# AVRI2CIO.net
KiCad netlist of a schematic drawn in EAGLE
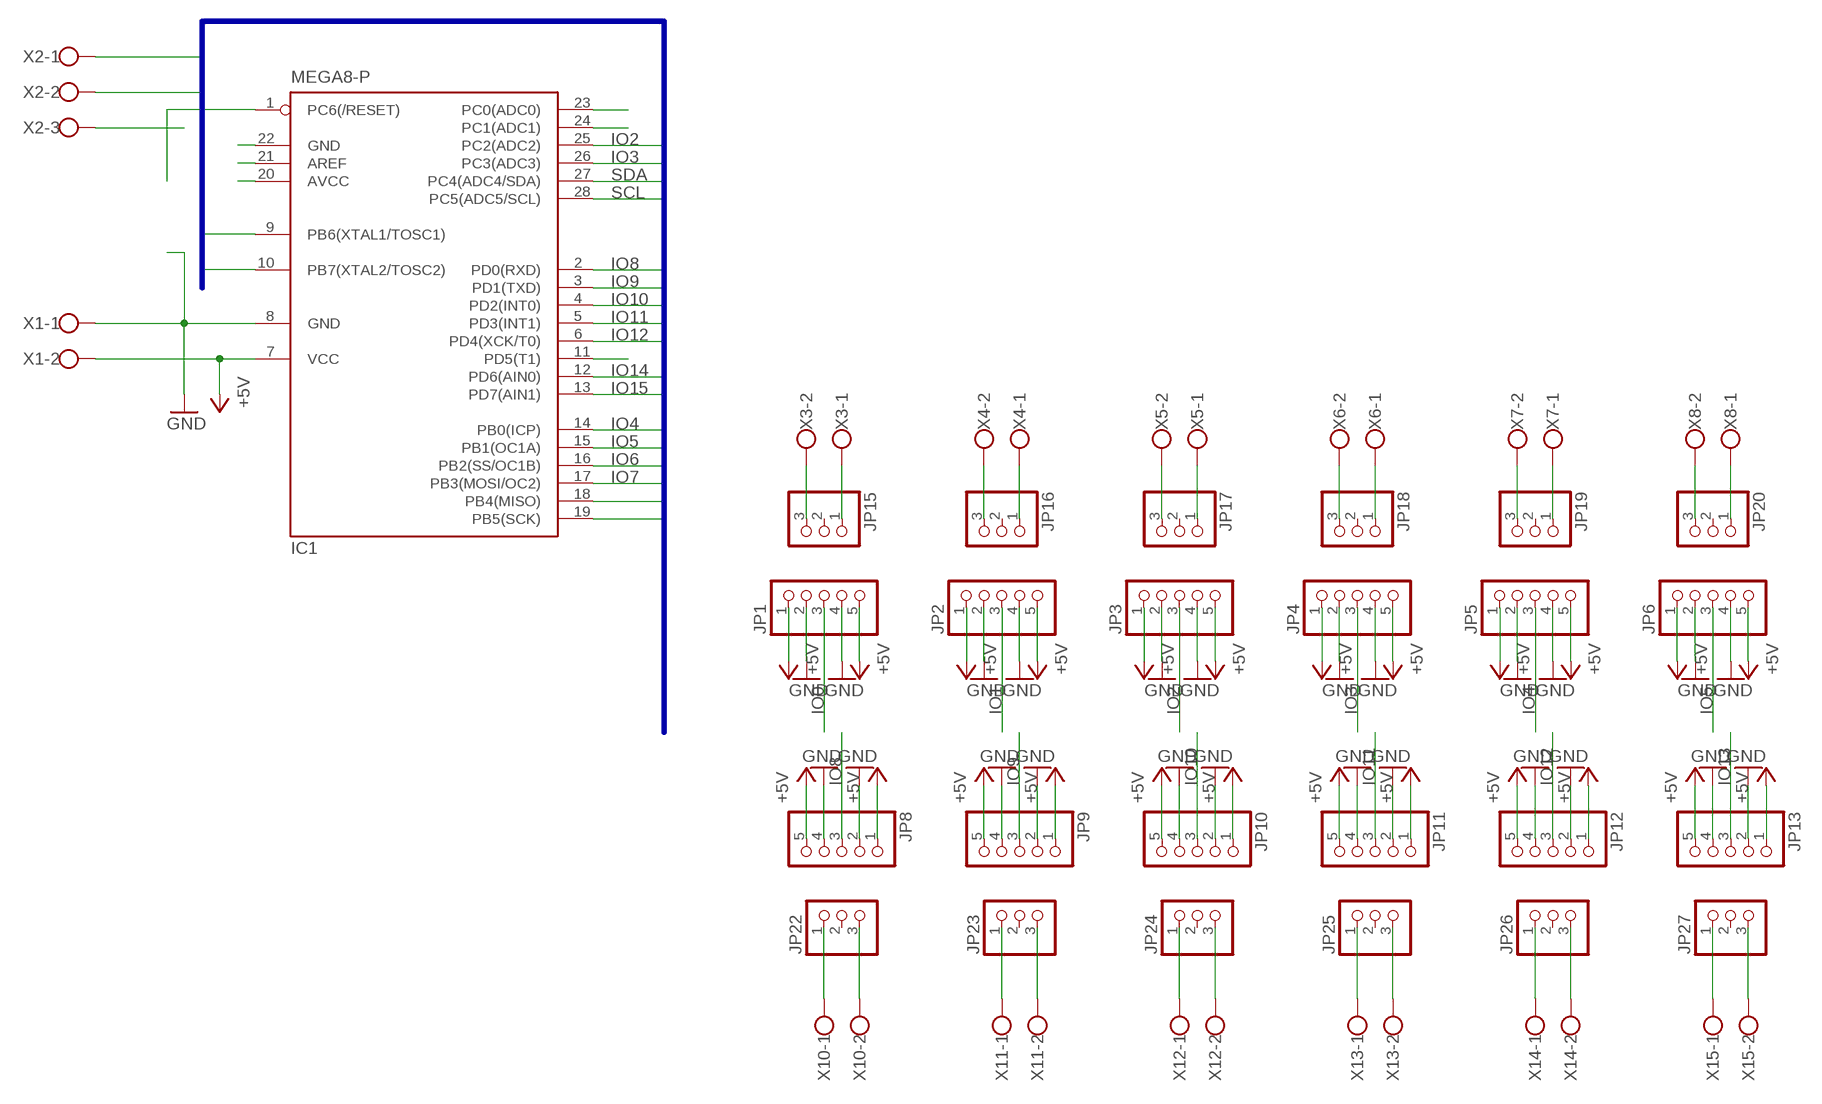
[diagram p0: schematic, sheet 1]

(export (version "E")
  (design (tool "Eeschema 10.0.6"))
  (components
    (comp (ref "IC1")
      (value "MEGA8-P")
      (footprint "eagle-import:DIL28-3")
      (libsource (lib "eagle-import") (part "MEGA8-P"))
    )
    (comp (ref "JP1")
      (value "PINHD-1X5")
      (footprint "eagle-import:1X05")
      (libsource (lib "eagle-import") (part "PINHD-1X5"))
    )
    (comp (ref "JP2")
      (value "PINHD-1X5")
      (footprint "eagle-import:1X05")
      (libsource (lib "eagle-import") (part "PINHD-1X5"))
    )
    (comp (ref "JP3")
      (value "PINHD-1X5")
      (footprint "eagle-import:1X05")
      (libsource (lib "eagle-import") (part "PINHD-1X5"))
    )
    (comp (ref "JP4")
      (value "PINHD-1X5")
      (footprint "eagle-import:1X05")
      (libsource (lib "eagle-import") (part "PINHD-1X5"))
    )
    (comp (ref "JP5")
      (value "PINHD-1X5")
      (footprint "eagle-import:1X05")
      (libsource (lib "eagle-import") (part "PINHD-1X5"))
    )
    (comp (ref "JP6")
      (value "PINHD-1X5")
      (footprint "eagle-import:1X05")
      (libsource (lib "eagle-import") (part "PINHD-1X5"))
    )
    (comp (ref "JP8")
      (value "PINHD-1X5")
      (footprint "eagle-import:1X05")
      (libsource (lib "eagle-import") (part "PINHD-1X5"))
    )
    (comp (ref "JP9")
      (value "PINHD-1X5")
      (footprint "eagle-import:1X05")
      (libsource (lib "eagle-import") (part "PINHD-1X5"))
    )
    (comp (ref "JP10")
      (value "PINHD-1X5")
      (footprint "eagle-import:1X05")
      (libsource (lib "eagle-import") (part "PINHD-1X5"))
    )
    (comp (ref "JP11")
      (value "PINHD-1X5")
      (footprint "eagle-import:1X05")
      (libsource (lib "eagle-import") (part "PINHD-1X5"))
    )
    (comp (ref "JP12")
      (value "PINHD-1X5")
      (footprint "eagle-import:1X05")
      (libsource (lib "eagle-import") (part "PINHD-1X5"))
    )
    (comp (ref "JP13")
      (value "PINHD-1X5")
      (footprint "eagle-import:1X05")
      (libsource (lib "eagle-import") (part "PINHD-1X5"))
    )
    (comp (ref "JP15")
      (value "PINHD-1X3")
      (footprint "eagle-import:1X03")
      (libsource (lib "eagle-import") (part "PINHD-1X3"))
    )
    (comp (ref "JP16")
      (value "PINHD-1X3")
      (footprint "eagle-import:1X03")
      (libsource (lib "eagle-import") (part "PINHD-1X3"))
    )
    (comp (ref "JP17")
      (value "PINHD-1X3")
      (footprint "eagle-import:1X03")
      (libsource (lib "eagle-import") (part "PINHD-1X3"))
    )
    (comp (ref "JP18")
      (value "PINHD-1X3")
      (footprint "eagle-import:1X03")
      (libsource (lib "eagle-import") (part "PINHD-1X3"))
    )
    (comp (ref "JP19")
      (value "PINHD-1X3")
      (footprint "eagle-import:1X03")
      (libsource (lib "eagle-import") (part "PINHD-1X3"))
    )
    (comp (ref "JP20")
      (value "PINHD-1X3")
      (footprint "eagle-import:1X03")
      (libsource (lib "eagle-import") (part "PINHD-1X3"))
    )
    (comp (ref "JP22")
      (value "PINHD-1X3")
      (footprint "eagle-import:1X03")
      (libsource (lib "eagle-import") (part "PINHD-1X3"))
    )
    (comp (ref "JP23")
      (value "PINHD-1X3")
      (footprint "eagle-import:1X03")
      (libsource (lib "eagle-import") (part "PINHD-1X3"))
    )
    (comp (ref "JP24")
      (value "PINHD-1X3")
      (footprint "eagle-import:1X03")
      (libsource (lib "eagle-import") (part "PINHD-1X3"))
    )
    (comp (ref "JP25")
      (value "PINHD-1X3")
      (footprint "eagle-import:1X03")
      (libsource (lib "eagle-import") (part "PINHD-1X3"))
    )
    (comp (ref "JP26")
      (value "PINHD-1X3")
      (footprint "eagle-import:1X03")
      (libsource (lib "eagle-import") (part "PINHD-1X3"))
    )
    (comp (ref "JP27")
      (value "PINHD-1X3")
      (footprint "eagle-import:1X03")
      (libsource (lib "eagle-import") (part "PINHD-1X3"))
    )
    (comp (ref "X1")
      (value "W237-102")
      (footprint "eagle-import:W237-102")
      (fields (field (name "MPN") "237-102"))
      (libsource (lib "eagle-import") (part "W237-102"))
    )
    (comp (ref "X2")
      (value "W237-103")
      (footprint "eagle-import:W237-103")
      (fields (field (name "MPN") "237-103"))
      (libsource (lib "eagle-import") (part "W237-103"))
    )
    (comp (ref "X3")
      (value "W237-102")
      (footprint "eagle-import:W237-102")
      (fields (field (name "MPN") "237-102"))
      (libsource (lib "eagle-import") (part "W237-102"))
    )
    (comp (ref "X4")
      (value "W237-102")
      (footprint "eagle-import:W237-102")
      (fields (field (name "MPN") "237-102"))
      (libsource (lib "eagle-import") (part "W237-102"))
    )
    (comp (ref "X5")
      (value "W237-102")
      (footprint "eagle-import:W237-102")
      (fields (field (name "MPN") "237-102"))
      (libsource (lib "eagle-import") (part "W237-102"))
    )
    (comp (ref "X6")
      (value "W237-102")
      (footprint "eagle-import:W237-102")
      (fields (field (name "MPN") "237-102"))
      (libsource (lib "eagle-import") (part "W237-102"))
    )
    (comp (ref "X7")
      (value "W237-102")
      (footprint "eagle-import:W237-102")
      (fields (field (name "MPN") "237-102"))
      (libsource (lib "eagle-import") (part "W237-102"))
    )
    (comp (ref "X8")
      (value "W237-102")
      (footprint "eagle-import:W237-102")
      (fields (field (name "MPN") "237-102"))
      (libsource (lib "eagle-import") (part "W237-102"))
    )
    (comp (ref "X10")
      (value "W237-102")
      (footprint "eagle-import:W237-102")
      (fields (field (name "MPN") "237-102"))
      (libsource (lib "eagle-import") (part "W237-102"))
    )
    (comp (ref "X11")
      (value "W237-102")
      (footprint "eagle-import:W237-102")
      (fields (field (name "MPN") "237-102"))
      (libsource (lib "eagle-import") (part "W237-102"))
    )
    (comp (ref "X12")
      (value "W237-102")
      (footprint "eagle-import:W237-102")
      (fields (field (name "MPN") "237-102"))
      (libsource (lib "eagle-import") (part "W237-102"))
    )
    (comp (ref "X13")
      (value "W237-102")
      (footprint "eagle-import:W237-102")
      (fields (field (name "MPN") "237-102"))
      (libsource (lib "eagle-import") (part "W237-102"))
    )
    (comp (ref "X14")
      (value "W237-102")
      (footprint "eagle-import:W237-102")
      (fields (field (name "MPN") "237-102"))
      (libsource (lib "eagle-import") (part "W237-102"))
    )
    (comp (ref "X15")
      (value "W237-102")
      (footprint "eagle-import:W237-102")
      (fields (field (name "MPN") "237-102"))
      (libsource (lib "eagle-import") (part "W237-102"))
    )
  )
  (nets
    (net (code "1") (name "+5V") (class "Default")
      (node (ref "IC1") (pin "7") (pinfunction "VCC_7") (pintype "power_in"))
      (node (ref "JP1") (pin "1") (pinfunction "1_1") (pintype "passive"))
      (node (ref "JP1") (pin "5") (pinfunction "5_5") (pintype "passive"))
      (node (ref "JP10") (pin "1") (pinfunction "1_1") (pintype "passive"))
      (node (ref "JP10") (pin "5") (pinfunction "5_5") (pintype "passive"))
      (node (ref "JP11") (pin "1") (pinfunction "1_1") (pintype "passive"))
      (node (ref "JP11") (pin "5") (pinfunction "5_5") (pintype "passive"))
      (node (ref "JP12") (pin "1") (pinfunction "1_1") (pintype "passive"))
      (node (ref "JP12") (pin "5") (pinfunction "5_5") (pintype "passive"))
      (node (ref "JP13") (pin "1") (pinfunction "1_1") (pintype "passive"))
      (node (ref "JP13") (pin "5") (pinfunction "5_5") (pintype "passive"))
      (node (ref "JP2") (pin "1") (pinfunction "1_1") (pintype "passive"))
      (node (ref "JP2") (pin "5") (pinfunction "5_5") (pintype "passive"))
      (node (ref "JP3") (pin "1") (pinfunction "1_1") (pintype "passive"))
      (node (ref "JP3") (pin "5") (pinfunction "5_5") (pintype "passive"))
      (node (ref "JP4") (pin "1") (pinfunction "1_1") (pintype "passive"))
      (node (ref "JP4") (pin "5") (pinfunction "5_5") (pintype "passive"))
      (node (ref "JP5") (pin "1") (pinfunction "1_1") (pintype "passive"))
      (node (ref "JP5") (pin "5") (pinfunction "5_5") (pintype "passive"))
      (node (ref "JP6") (pin "1") (pinfunction "1_1") (pintype "passive"))
      (node (ref "JP6") (pin "5") (pinfunction "5_5") (pintype "passive"))
      (node (ref "JP8") (pin "1") (pinfunction "1_1") (pintype "passive"))
      (node (ref "JP8") (pin "5") (pinfunction "5_5") (pintype "passive"))
      (node (ref "JP9") (pin "1") (pinfunction "1_1") (pintype "passive"))
      (node (ref "JP9") (pin "5") (pinfunction "5_5") (pintype "passive"))
      (node (ref "X1") (pin "2") (pinfunction "KL_2") (pintype "passive"))
    )
    (net (code "2") (name "/IO0") (class "Default")
      (node (ref "IC1") (pin "11") (pinfunction "PD5(T1)_11") (pintype "bidirectional"))
      (node (ref "JP1") (pin "3") (pinfunction "3_3") (pintype "passive"))
    )
    (net (code "3") (name "/IO1") (class "Default")
      (node (ref "IC1") (pin "9") (pinfunction "PB6(XTAL1/TOSC1)_9") (pintype "bidirectional"))
      (node (ref "JP2") (pin "3") (pinfunction "3_3") (pintype "passive"))
    )
    (net (code "4") (name "/IO2") (class "Default")
      (node (ref "IC1") (pin "25") (pinfunction "PC2(ADC2)_25") (pintype "bidirectional"))
      (node (ref "JP3") (pin "3") (pinfunction "3_3") (pintype "passive"))
    )
    (net (code "5") (name "/IO3") (class "Default")
      (node (ref "IC1") (pin "26") (pinfunction "PC3(ADC3)_26") (pintype "bidirectional"))
      (node (ref "JP4") (pin "3") (pinfunction "3_3") (pintype "passive"))
    )
    (net (code "6") (name "/IO4") (class "Default")
      (node (ref "IC1") (pin "14") (pinfunction "PB0(ICP)_14") (pintype "bidirectional"))
      (node (ref "JP5") (pin "3") (pinfunction "3_3") (pintype "passive"))
    )
    (net (code "7") (name "/IO5") (class "Default")
      (node (ref "IC1") (pin "15") (pinfunction "PB1(OC1A)_15") (pintype "bidirectional"))
      (node (ref "JP6") (pin "3") (pinfunction "3_3") (pintype "passive"))
    )
    (net (code "8") (name "/IO6") (class "Default")
      (node (ref "IC1") (pin "16") (pinfunction "PB2(SS/OC1B)_16") (pintype "bidirectional"))
    )
    (net (code "9") (name "/IO7") (class "Default")
      (node (ref "IC1") (pin "17") (pinfunction "PB3(MOSI/OC2)_17") (pintype "bidirectional"))
    )
    (net (code "10") (name "/IO8") (class "Default")
      (node (ref "IC1") (pin "2") (pinfunction "PD0(RXD)_2") (pintype "bidirectional"))
      (node (ref "JP8") (pin "3") (pinfunction "3_3") (pintype "passive"))
    )
    (net (code "11") (name "/IO9") (class "Default")
      (node (ref "IC1") (pin "3") (pinfunction "PD1(TXD)_3") (pintype "bidirectional"))
      (node (ref "JP9") (pin "3") (pinfunction "3_3") (pintype "passive"))
    )
    (net (code "12") (name "/IO10") (class "Default")
      (node (ref "IC1") (pin "4") (pinfunction "PD2(INT0)_4") (pintype "bidirectional"))
      (node (ref "JP10") (pin "3") (pinfunction "3_3") (pintype "passive"))
    )
    (net (code "13") (name "/IO11") (class "Default")
      (node (ref "IC1") (pin "5") (pinfunction "PD3(INT1)_5") (pintype "bidirectional"))
      (node (ref "JP11") (pin "3") (pinfunction "3_3") (pintype "passive"))
    )
    (net (code "14") (name "/IO12") (class "Default")
      (node (ref "IC1") (pin "6") (pinfunction "PD4(XCK/T0)_6") (pintype "bidirectional"))
      (node (ref "JP12") (pin "3") (pinfunction "3_3") (pintype "passive"))
    )
    (net (code "15") (name "/IO13") (class "Default")
      (node (ref "IC1") (pin "10") (pinfunction "PB7(XTAL2/TOSC2)_10") (pintype "bidirectional"))
      (node (ref "JP13") (pin "3") (pinfunction "3_3") (pintype "passive"))
    )
    (net (code "16") (name "/IO14") (class "Default")
      (node (ref "IC1") (pin "12") (pinfunction "PD6(AIN0)_12") (pintype "bidirectional"))
    )
    (net (code "17") (name "/IO15") (class "Default")
      (node (ref "IC1") (pin "13") (pinfunction "PD7(AIN1)_13") (pintype "bidirectional"))
    )
    (net (code "18") (name "/SCL") (class "Default")
      (node (ref "IC1") (pin "28") (pinfunction "PC5(ADC5/SCL)_28") (pintype "bidirectional"))
      (node (ref "X2") (pin "2") (pinfunction "KL_2") (pintype "passive"))
    )
    (net (code "19") (name "/SDA") (class "Default")
      (node (ref "IC1") (pin "27") (pinfunction "PC4(ADC4/SDA)_27") (pintype "bidirectional"))
      (node (ref "X2") (pin "3") (pinfunction "KL_3") (pintype "passive"))
    )
    (net (code "20") (name "GND") (class "Default")
      (node (ref "IC1") (pin "8") (pinfunction "GND_8") (pintype "power_in"))
      (node (ref "JP1") (pin "2") (pinfunction "2_2") (pintype "passive"))
      (node (ref "JP1") (pin "4") (pinfunction "4_4") (pintype "passive"))
      (node (ref "JP10") (pin "2") (pinfunction "2_2") (pintype "passive"))
      (node (ref "JP10") (pin "4") (pinfunction "4_4") (pintype "passive"))
      (node (ref "JP11") (pin "2") (pinfunction "2_2") (pintype "passive"))
      (node (ref "JP11") (pin "4") (pinfunction "4_4") (pintype "passive"))
      (node (ref "JP12") (pin "2") (pinfunction "2_2") (pintype "passive"))
      (node (ref "JP12") (pin "4") (pinfunction "4_4") (pintype "passive"))
      (node (ref "JP13") (pin "2") (pinfunction "2_2") (pintype "passive"))
      (node (ref "JP13") (pin "4") (pinfunction "4_4") (pintype "passive"))
      (node (ref "JP2") (pin "2") (pinfunction "2_2") (pintype "passive"))
      (node (ref "JP2") (pin "4") (pinfunction "4_4") (pintype "passive"))
      (node (ref "JP3") (pin "2") (pinfunction "2_2") (pintype "passive"))
      (node (ref "JP3") (pin "4") (pinfunction "4_4") (pintype "passive"))
      (node (ref "JP4") (pin "2") (pinfunction "2_2") (pintype "passive"))
      (node (ref "JP4") (pin "4") (pinfunction "4_4") (pintype "passive"))
      (node (ref "JP5") (pin "2") (pinfunction "2_2") (pintype "passive"))
      (node (ref "JP5") (pin "4") (pinfunction "4_4") (pintype "passive"))
      (node (ref "JP6") (pin "2") (pinfunction "2_2") (pintype "passive"))
      (node (ref "JP6") (pin "4") (pinfunction "4_4") (pintype "passive"))
      (node (ref "JP8") (pin "2") (pinfunction "2_2") (pintype "passive"))
      (node (ref "JP8") (pin "4") (pinfunction "4_4") (pintype "passive"))
      (node (ref "JP9") (pin "2") (pinfunction "2_2") (pintype "passive"))
      (node (ref "JP9") (pin "4") (pinfunction "4_4") (pintype "passive"))
      (node (ref "X1") (pin "1") (pinfunction "KL_1") (pintype "passive"))
      (node (ref "X2") (pin "1") (pinfunction "KL_1") (pintype "passive"))
    )
    (net (code "21") (name "Net-(X3A-KL)") (class "Default")
      (node (ref "JP15") (pin "1") (pinfunction "1_1") (pintype "passive"))
      (node (ref "X3") (pin "1") (pinfunction "KL_1") (pintype "passive"))
    )
    (net (code "22") (name "Net-(X3B-KL)") (class "Default")
      (node (ref "JP15") (pin "3") (pinfunction "3_3") (pintype "passive"))
      (node (ref "X3") (pin "2") (pinfunction "KL_2") (pintype "passive"))
    )
    (net (code "23") (name "Net-(X4A-KL)") (class "Default")
      (node (ref "JP16") (pin "1") (pinfunction "1_1") (pintype "passive"))
      (node (ref "X4") (pin "1") (pinfunction "KL_1") (pintype "passive"))
    )
    (net (code "24") (name "Net-(X4B-KL)") (class "Default")
      (node (ref "JP16") (pin "3") (pinfunction "3_3") (pintype "passive"))
      (node (ref "X4") (pin "2") (pinfunction "KL_2") (pintype "passive"))
    )
    (net (code "25") (name "Net-(X5A-KL)") (class "Default")
      (node (ref "JP17") (pin "1") (pinfunction "1_1") (pintype "passive"))
      (node (ref "X5") (pin "1") (pinfunction "KL_1") (pintype "passive"))
    )
    (net (code "26") (name "Net-(X5B-KL)") (class "Default")
      (node (ref "JP17") (pin "3") (pinfunction "3_3") (pintype "passive"))
      (node (ref "X5") (pin "2") (pinfunction "KL_2") (pintype "passive"))
    )
    (net (code "27") (name "Net-(X6A-KL)") (class "Default")
      (node (ref "JP18") (pin "1") (pinfunction "1_1") (pintype "passive"))
      (node (ref "X6") (pin "1") (pinfunction "KL_1") (pintype "passive"))
    )
    (net (code "28") (name "Net-(X6B-KL)") (class "Default")
      (node (ref "JP18") (pin "3") (pinfunction "3_3") (pintype "passive"))
      (node (ref "X6") (pin "2") (pinfunction "KL_2") (pintype "passive"))
    )
    (net (code "29") (name "Net-(X7A-KL)") (class "Default")
      (node (ref "JP19") (pin "1") (pinfunction "1_1") (pintype "passive"))
      (node (ref "X7") (pin "1") (pinfunction "KL_1") (pintype "passive"))
    )
    (net (code "30") (name "Net-(X7B-KL)") (class "Default")
      (node (ref "JP19") (pin "3") (pinfunction "3_3") (pintype "passive"))
      (node (ref "X7") (pin "2") (pinfunction "KL_2") (pintype "passive"))
    )
    (net (code "31") (name "Net-(X8A-KL)") (class "Default")
      (node (ref "JP20") (pin "1") (pinfunction "1_1") (pintype "passive"))
      (node (ref "X8") (pin "1") (pinfunction "KL_1") (pintype "passive"))
    )
    (net (code "32") (name "Net-(X8B-KL)") (class "Default")
      (node (ref "JP20") (pin "3") (pinfunction "3_3") (pintype "passive"))
      (node (ref "X8") (pin "2") (pinfunction "KL_2") (pintype "passive"))
    )
    (net (code "33") (name "Net-(X10A-KL)") (class "Default")
      (node (ref "JP22") (pin "1") (pinfunction "1_1") (pintype "passive"))
      (node (ref "X10") (pin "1") (pinfunction "KL_1") (pintype "passive"))
    )
    (net (code "34") (name "Net-(X10B-KL)") (class "Default")
      (node (ref "JP22") (pin "3") (pinfunction "3_3") (pintype "passive"))
      (node (ref "X10") (pin "2") (pinfunction "KL_2") (pintype "passive"))
    )
    (net (code "35") (name "Net-(X11A-KL)") (class "Default")
      (node (ref "JP23") (pin "1") (pinfunction "1_1") (pintype "passive"))
      (node (ref "X11") (pin "1") (pinfunction "KL_1") (pintype "passive"))
    )
    (net (code "36") (name "Net-(X11B-KL)") (class "Default")
      (node (ref "JP23") (pin "3") (pinfunction "3_3") (pintype "passive"))
      (node (ref "X11") (pin "2") (pinfunction "KL_2") (pintype "passive"))
    )
    (net (code "37") (name "Net-(X12A-KL)") (class "Default")
      (node (ref "JP24") (pin "1") (pinfunction "1_1") (pintype "passive"))
      (node (ref "X12") (pin "1") (pinfunction "KL_1") (pintype "passive"))
    )
    (net (code "38") (name "Net-(X12B-KL)") (class "Default")
      (node (ref "JP24") (pin "3") (pinfunction "3_3") (pintype "passive"))
      (node (ref "X12") (pin "2") (pinfunction "KL_2") (pintype "passive"))
    )
    (net (code "39") (name "Net-(X13A-KL)") (class "Default")
      (node (ref "JP25") (pin "1") (pinfunction "1_1") (pintype "passive"))
      (node (ref "X13") (pin "1") (pinfunction "KL_1") (pintype "passive"))
    )
    (net (code "40") (name "Net-(X13B-KL)") (class "Default")
      (node (ref "JP25") (pin "3") (pinfunction "3_3") (pintype "passive"))
      (node (ref "X13") (pin "2") (pinfunction "KL_2") (pintype "passive"))
    )
    (net (code "41") (name "Net-(X14A-KL)") (class "Default")
      (node (ref "JP26") (pin "1") (pinfunction "1_1") (pintype "passive"))
      (node (ref "X14") (pin "1") (pinfunction "KL_1") (pintype "passive"))
    )
    (net (code "42") (name "Net-(X14B-KL)") (class "Default")
      (node (ref "JP26") (pin "3") (pinfunction "3_3") (pintype "passive"))
      (node (ref "X14") (pin "2") (pinfunction "KL_2") (pintype "passive"))
    )
    (net (code "43") (name "Net-(X15A-KL)") (class "Default")
      (node (ref "JP27") (pin "1") (pinfunction "1_1") (pintype "passive"))
      (node (ref "X15") (pin "1") (pinfunction "KL_1") (pintype "passive"))
    )
    (net (code "44") (name "Net-(X15B-KL)") (class "Default")
      (node (ref "JP27") (pin "3") (pinfunction "3_3") (pintype "passive"))
      (node (ref "X15") (pin "2") (pinfunction "KL_2") (pintype "passive"))
    )
    (net (code "45") (name "unconnected-(IC1-AREF-Pad21)") (class "Default")
      (node (ref "IC1") (pin "21") (pinfunction "AREF_21") (pintype "passive"))
    )
    (net (code "46") (name "unconnected-(IC1-AVCC-Pad20)") (class "Default")
      (node (ref "IC1") (pin "20") (pinfunction "AVCC_20") (pintype "power_in"))
    )
    (net (code "47") (name "unconnected-(IC1-GND-Pad22)") (class "Default")
      (node (ref "IC1") (pin "22") (pinfunction "GND_22") (pintype "power_in"))
    )
    (net (code "48") (name "unconnected-(IC1-PB4(MISO)-Pad18)") (class "Default")
      (node (ref "IC1") (pin "18") (pinfunction "PB4(MISO)_18") (pintype "bidirectional"))
    )
    (net (code "49") (name "unconnected-(IC1-PB5(SCK)-Pad19)") (class "Default")
      (node (ref "IC1") (pin "19") (pinfunction "PB5(SCK)_19") (pintype "bidirectional"))
    )
    (net (code "50") (name "unconnected-(IC1-PC0(ADC0)-Pad23)") (class "Default")
      (node (ref "IC1") (pin "23") (pinfunction "PC0(ADC0)_23") (pintype "bidirectional"))
    )
    (net (code "51") (name "unconnected-(IC1-PC1(ADC1)-Pad24)") (class "Default")
      (node (ref "IC1") (pin "24") (pinfunction "PC1(ADC1)_24") (pintype "bidirectional"))
    )
    (net (code "52") (name "unconnected-(IC1-PC6({slash}RESET)-Pad1)") (class "Default")
      (node (ref "IC1") (pin "1") (pinfunction "PC6(/RESET)_1") (pintype "bidirectional"))
    )
    (net (code "53") (name "unconnected-(JP15-Pad2)") (class "Default")
      (node (ref "JP15") (pin "2") (pinfunction "2_2") (pintype "passive"))
    )
    (net (code "54") (name "unconnected-(JP16-Pad2)") (class "Default")
      (node (ref "JP16") (pin "2") (pinfunction "2_2") (pintype "passive"))
    )
    (net (code "55") (name "unconnected-(JP17-Pad2)") (class "Default")
      (node (ref "JP17") (pin "2") (pinfunction "2_2") (pintype "passive"))
    )
    (net (code "56") (name "unconnected-(JP18-Pad2)") (class "Default")
      (node (ref "JP18") (pin "2") (pinfunction "2_2") (pintype "passive"))
    )
    (net (code "57") (name "unconnected-(JP19-Pad2)") (class "Default")
      (node (ref "JP19") (pin "2") (pinfunction "2_2") (pintype "passive"))
    )
    (net (code "58") (name "unconnected-(JP20-Pad2)") (class "Default")
      (node (ref "JP20") (pin "2") (pinfunction "2_2") (pintype "passive"))
    )
    (net (code "59") (name "unconnected-(JP22-Pad2)") (class "Default")
      (node (ref "JP22") (pin "2") (pinfunction "2_2") (pintype "passive"))
    )
    (net (code "60") (name "unconnected-(JP23-Pad2)") (class "Default")
      (node (ref "JP23") (pin "2") (pinfunction "2_2") (pintype "passive"))
    )
    (net (code "61") (name "unconnected-(JP24-Pad2)") (class "Default")
      (node (ref "JP24") (pin "2") (pinfunction "2_2") (pintype "passive"))
    )
    (net (code "62") (name "unconnected-(JP25-Pad2)") (class "Default")
      (node (ref "JP25") (pin "2") (pinfunction "2_2") (pintype "passive"))
    )
    (net (code "63") (name "unconnected-(JP26-Pad2)") (class "Default")
      (node (ref "JP26") (pin "2") (pinfunction "2_2") (pintype "passive"))
    )
    (net (code "64") (name "unconnected-(JP27-Pad2)") (class "Default")
      (node (ref "JP27") (pin "2") (pinfunction "2_2") (pintype "passive"))
    )
  )
)
